# LR2051-901-input-panel.net
KiCad netlist of a schematic drawn in EAGLE
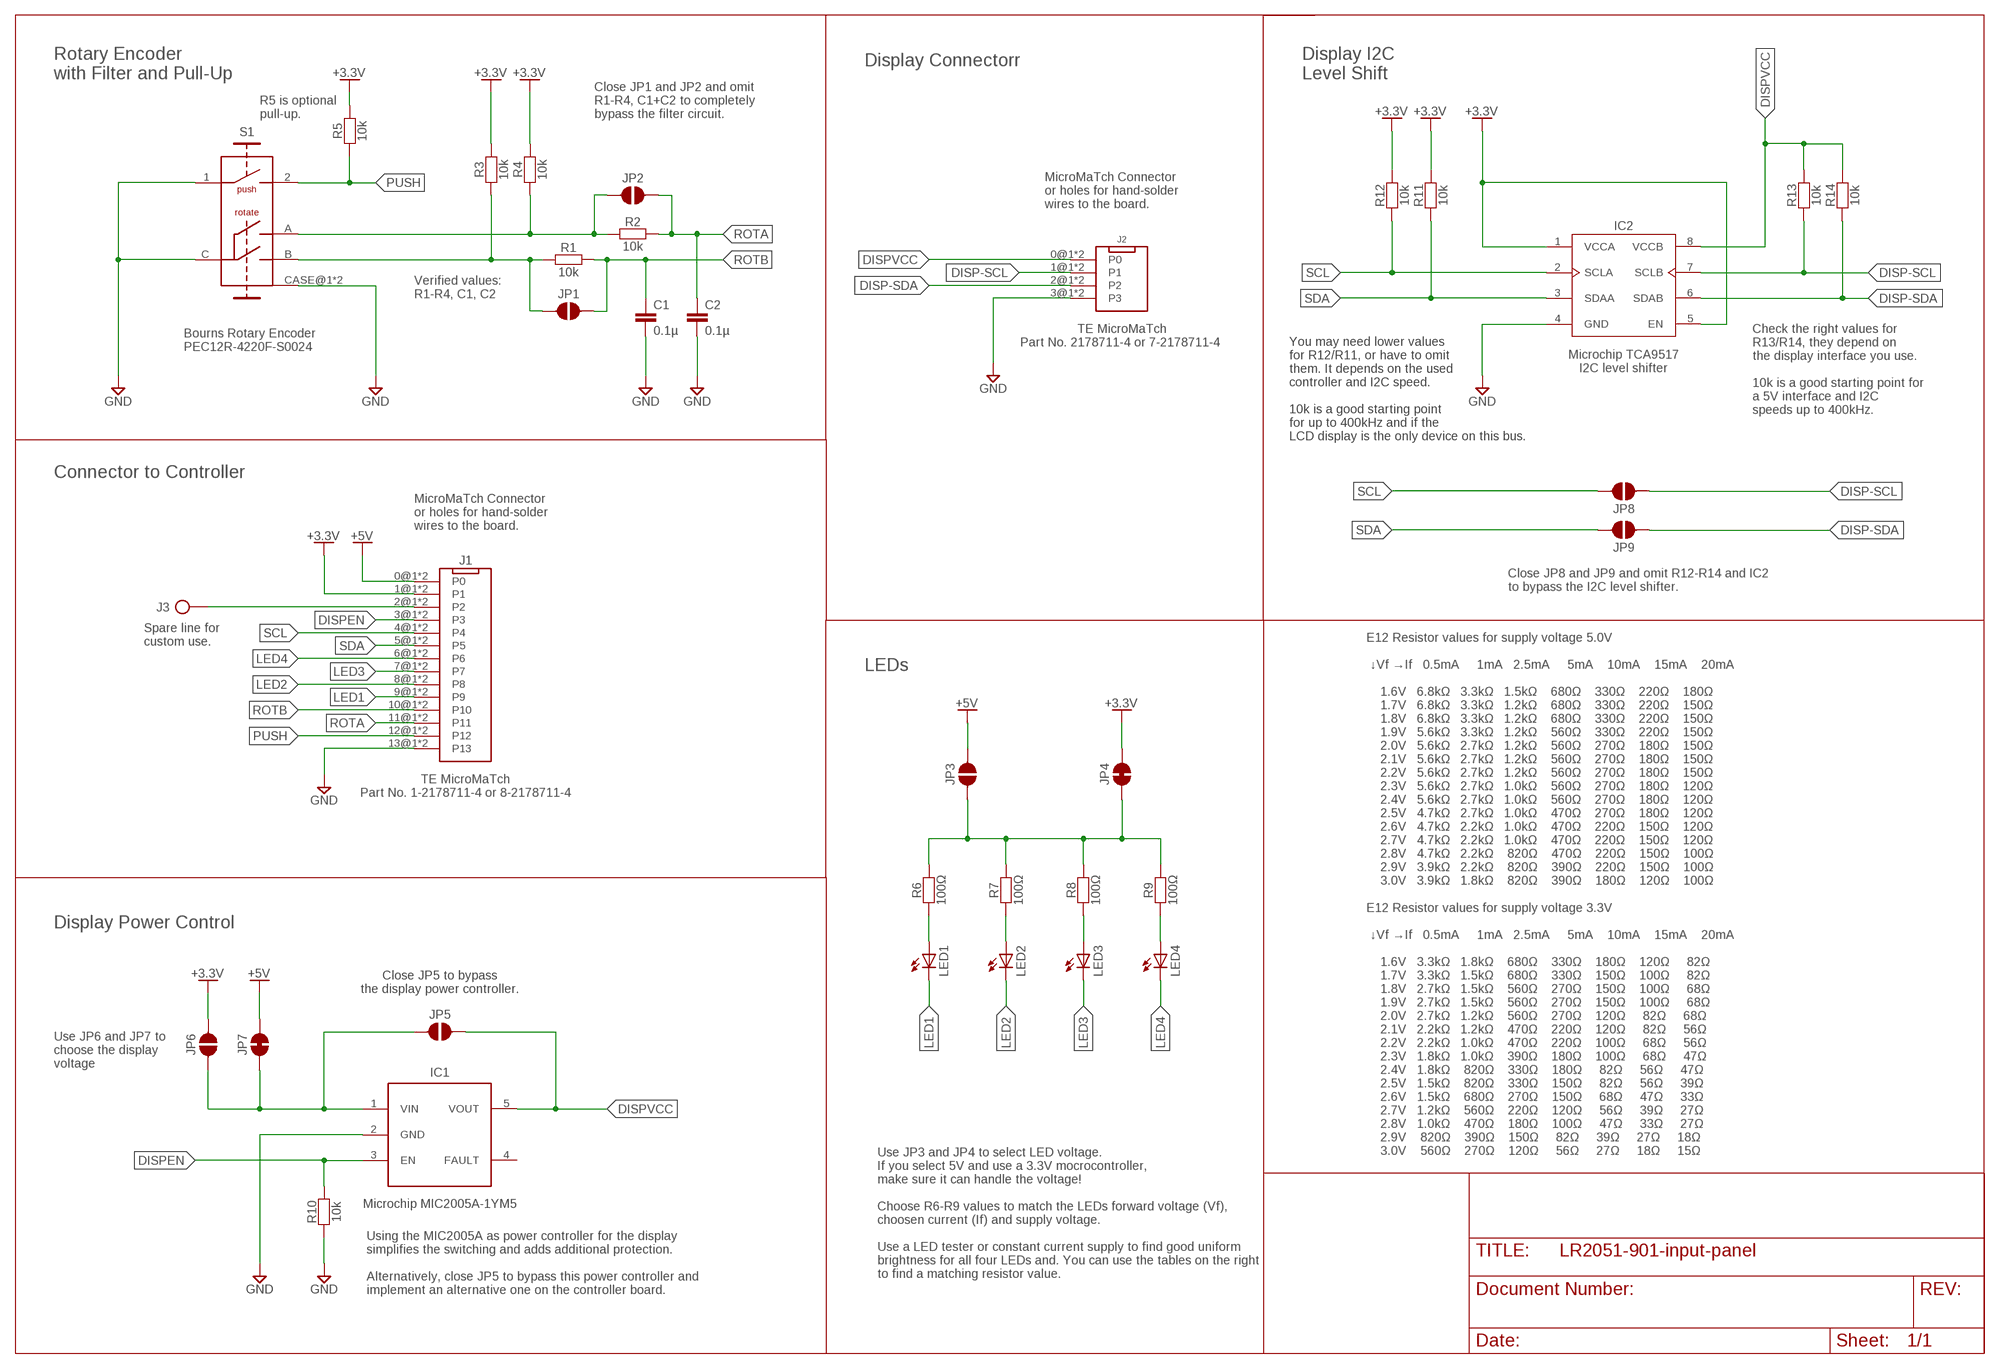
[diagram p0: schematic, sheet 1]

(export (version "E")
  (design (tool "Eeschema 10.0.6"))
  (components
    (comp (ref "C1")
      (value "0.1µ")
      (footprint "eagle-import:CAPACITOR-0805-VISHAY")
      (libsource (lib "eagle-import") (part "C0805-VISHAY"))
    )
    (comp (ref "C2")
      (value "0.1µ")
      (footprint "eagle-import:CAPACITOR-0805-VISHAY")
      (libsource (lib "eagle-import") (part "C0805-VISHAY"))
    )
    (comp (ref "IC1")
      (value "IC-MIC2005A-1YM5")
      (footprint "eagle-import:SOT23-5")
      (libsource (lib "eagle-import") (part "IC-MIC2005A-1YM5"))
    )
    (comp (ref "IC2")
      (value "IC-TCA9517")
      (footprint "eagle-import:SOIC127P599X175-8N")
      (libsource (lib "eagle-import") (part "IC-TCA9517"))
    )
    (comp (ref "J1")
      (value "CON-TE-MICROMATCH-14P-SMD+TH")
      (footprint "eagle-import:CON-TE-MICROMATCH-1-2178711-4+TH")
      (libsource (lib "eagle-import") (part "CON-TE-MICROMATCH-14P-SMD+TH"))
    )
    (comp (ref "J2")
      (value "CON-TE-MICROMATCH-4P-SMD+TH")
      (footprint "eagle-import:CON-TE-MICROMATCH-2178711-4+TH")
      (libsource (lib "eagle-import") (part "CON-TE-MICROMATCH-4P-SMD+TH"))
    )
    (comp (ref "J3")
      (value "CON-HOLE-D0.9")
      (footprint "eagle-import:CON-HOLE-D0.9")
      (libsource (lib "eagle-import") (part "CON-HOLE-D0.9"))
    )
    (comp (ref "JP1")
      (value "J-SMD-OFF")
      (footprint "eagle-import:J-SMD-OFF")
      (libsource (lib "eagle-import") (part "J-SMD-OFF"))
    )
    (comp (ref "JP2")
      (value "J-SMD-OFF")
      (footprint "eagle-import:J-SMD-OFF")
      (libsource (lib "eagle-import") (part "J-SMD-OFF"))
    )
    (comp (ref "JP3")
      (value "J-SMD-OFF")
      (footprint "eagle-import:J-SMD-OFF")
      (libsource (lib "eagle-import") (part "J-SMD-OFF"))
    )
    (comp (ref "JP4")
      (value "J-SMD-ON")
      (footprint "eagle-import:J-SMD-ON")
      (libsource (lib "eagle-import") (part "J-SMD-ON"))
    )
    (comp (ref "JP5")
      (value "J-SMD-OFF")
      (footprint "eagle-import:J-SMD-OFF")
      (libsource (lib "eagle-import") (part "J-SMD-OFF"))
    )
    (comp (ref "JP6")
      (value "J-SMD-OFF")
      (footprint "eagle-import:J-SMD-OFF")
      (libsource (lib "eagle-import") (part "J-SMD-OFF"))
    )
    (comp (ref "JP7")
      (value "J-SMD-ON")
      (footprint "eagle-import:J-SMD-ON")
      (libsource (lib "eagle-import") (part "J-SMD-ON"))
    )
    (comp (ref "JP8")
      (value "J-SMD-OFF")
      (footprint "eagle-import:J-SMD-OFF")
      (libsource (lib "eagle-import") (part "J-SMD-OFF"))
    )
    (comp (ref "JP9")
      (value "J-SMD-OFF")
      (footprint "eagle-import:J-SMD-OFF")
      (libsource (lib "eagle-import") (part "J-SMD-OFF"))
    )
    (comp (ref "LED1")
      (value "LED5MM")
      (footprint "eagle-import:LED5MM")
      (libsource (lib "eagle-import") (part "LED5MM"))
    )
    (comp (ref "LED2")
      (value "LED5MM")
      (footprint "eagle-import:LED5MM")
      (libsource (lib "eagle-import") (part "LED5MM"))
    )
    (comp (ref "LED3")
      (value "LED5MM")
      (footprint "eagle-import:LED5MM")
      (libsource (lib "eagle-import") (part "LED5MM"))
    )
    (comp (ref "LED4")
      (value "LED5MM")
      (footprint "eagle-import:LED5MM")
      (libsource (lib "eagle-import") (part "LED5MM"))
    )
    (comp (ref "R1")
      (value "10k")
      (footprint "eagle-import:R-0805-HANDSOLDER")
      (libsource (lib "eagle-import") (part "R-0805-HANDSOLDER"))
    )
    (comp (ref "R2")
      (value "10k")
      (footprint "eagle-import:R-0805-HANDSOLDER")
      (libsource (lib "eagle-import") (part "R-0805-HANDSOLDER"))
    )
    (comp (ref "R3")
      (value "10k")
      (footprint "eagle-import:R-0805-HANDSOLDER")
      (libsource (lib "eagle-import") (part "R-0805-HANDSOLDER"))
    )
    (comp (ref "R4")
      (value "10k")
      (footprint "eagle-import:R-0805-HANDSOLDER")
      (libsource (lib "eagle-import") (part "R-0805-HANDSOLDER"))
    )
    (comp (ref "R5")
      (value "10k")
      (footprint "eagle-import:R-0805-HANDSOLDER")
      (libsource (lib "eagle-import") (part "R-0805-HANDSOLDER"))
    )
    (comp (ref "R6")
      (value "100Ω")
      (footprint "eagle-import:R-0805-HANDSOLDER")
      (libsource (lib "eagle-import") (part "R-0805-HANDSOLDER"))
    )
    (comp (ref "R7")
      (value "100Ω")
      (footprint "eagle-import:R-0805-HANDSOLDER")
      (libsource (lib "eagle-import") (part "R-0805-HANDSOLDER"))
    )
    (comp (ref "R8")
      (value "100Ω")
      (footprint "eagle-import:R-0805-HANDSOLDER")
      (libsource (lib "eagle-import") (part "R-0805-HANDSOLDER"))
    )
    (comp (ref "R9")
      (value "100Ω")
      (footprint "eagle-import:R-0805-HANDSOLDER")
      (libsource (lib "eagle-import") (part "R-0805-HANDSOLDER"))
    )
    (comp (ref "R10")
      (value "10k")
      (footprint "eagle-import:R-0805-HANDSOLDER")
      (libsource (lib "eagle-import") (part "R-0805-HANDSOLDER"))
    )
    (comp (ref "R11")
      (value "10k")
      (footprint "eagle-import:R-0805-HANDSOLDER")
      (libsource (lib "eagle-import") (part "R-0805-HANDSOLDER"))
    )
    (comp (ref "R12")
      (value "10k")
      (footprint "eagle-import:R-0805-HANDSOLDER")
      (libsource (lib "eagle-import") (part "R-0805-HANDSOLDER"))
    )
    (comp (ref "R13")
      (value "10k")
      (footprint "eagle-import:R-0805-HANDSOLDER")
      (libsource (lib "eagle-import") (part "R-0805-HANDSOLDER"))
    )
    (comp (ref "R14")
      (value "10k")
      (footprint "eagle-import:R-0805-HANDSOLDER")
      (libsource (lib "eagle-import") (part "R-0805-HANDSOLDER"))
    )
    (comp (ref "S1")
      (value "ENC-BOURNS-PEC12R-4220F-S0024")
      (footprint "eagle-import:ENC-BOURNS-PEC12R-4220F-S0024")
      (libsource (lib "eagle-import") (part "ENC-BOURNS-PEC12R-4220F-S0024"))
    )
  )
  (nets
    (net (code "1") (name "+3.3V") (class "Default")
      (node (ref "IC2") (pin "1") (pinfunction "VCCA_1") (pintype "power_in"))
      (node (ref "IC2") (pin "5") (pinfunction "EN_5") (pintype "bidirectional"))
      (node (ref "J1") (pin "1@1") (pinfunction "P1_1@1") (pintype "bidirectional"))
      (node (ref "J1") (pin "1@2") (pinfunction "P1_1@2") (pintype "bidirectional"))
      (node (ref "JP4") (pin "2") (pinfunction "2_2") (pintype "passive"))
      (node (ref "JP6") (pin "2") (pinfunction "2_2") (pintype "passive"))
      (node (ref "R11") (pin "2") (pinfunction "P2_2") (pintype "passive"))
      (node (ref "R12") (pin "2") (pinfunction "P2_2") (pintype "passive"))
      (node (ref "R3") (pin "2") (pinfunction "P2_2") (pintype "passive"))
      (node (ref "R4") (pin "2") (pinfunction "P2_2") (pintype "passive"))
      (node (ref "R5") (pin "2") (pinfunction "P2_2") (pintype "passive"))
    )
    (net (code "2") (name "+5V") (class "Default")
      (node (ref "J1") (pin "0@1") (pinfunction "P0_0@1") (pintype "bidirectional"))
      (node (ref "J1") (pin "0@2") (pinfunction "P0_0@2") (pintype "bidirectional"))
      (node (ref "JP3") (pin "2") (pinfunction "2_2") (pintype "passive"))
      (node (ref "JP7") (pin "2") (pinfunction "2_2") (pintype "passive"))
    )
    (net (code "3") (name "DISP-SCL") (class "Default")
      (node (ref "IC2") (pin "7") (pinfunction "SCLB_7") (pintype "bidirectional"))
      (node (ref "J2") (pin "1@1") (pinfunction "P1_1@1") (pintype "bidirectional"))
      (node (ref "J2") (pin "1@2") (pinfunction "P1_1@2") (pintype "bidirectional"))
      (node (ref "JP8") (pin "1") (pinfunction "1_1") (pintype "passive"))
      (node (ref "R13") (pin "1") (pinfunction "P1_1") (pintype "passive"))
    )
    (net (code "4") (name "DISP-SDA") (class "Default")
      (node (ref "IC2") (pin "6") (pinfunction "SDAB_6") (pintype "bidirectional"))
      (node (ref "J2") (pin "2@1") (pinfunction "P2_2@1") (pintype "bidirectional"))
      (node (ref "J2") (pin "2@2") (pinfunction "P2_2@2") (pintype "bidirectional"))
      (node (ref "JP9") (pin "1") (pinfunction "1_1") (pintype "passive"))
      (node (ref "R14") (pin "1") (pinfunction "P1_1") (pintype "passive"))
    )
    (net (code "5") (name "DISPEN") (class "Default")
      (node (ref "IC1") (pin "3") (pinfunction "EN_3") (pintype "input"))
      (node (ref "J1") (pin "3@1") (pinfunction "P3_3@1") (pintype "bidirectional"))
      (node (ref "J1") (pin "3@2") (pinfunction "P3_3@2") (pintype "bidirectional"))
      (node (ref "R10") (pin "2") (pinfunction "P2_2") (pintype "passive"))
    )
    (net (code "6") (name "DISPVCC") (class "Default")
      (node (ref "IC1") (pin "5") (pinfunction "VOUT_5") (pintype "power_in"))
      (node (ref "IC2") (pin "8") (pinfunction "VCCB_8") (pintype "power_in"))
      (node (ref "J2") (pin "0@1") (pinfunction "P0_0@1") (pintype "bidirectional"))
      (node (ref "J2") (pin "0@2") (pinfunction "P0_0@2") (pintype "bidirectional"))
      (node (ref "JP5") (pin "2") (pinfunction "2_2") (pintype "passive"))
      (node (ref "R13") (pin "2") (pinfunction "P2_2") (pintype "passive"))
      (node (ref "R14") (pin "2") (pinfunction "P2_2") (pintype "passive"))
    )
    (net (code "7") (name "GND") (class "Default")
      (node (ref "C1") (pin "2") (pinfunction "2_2") (pintype "passive"))
      (node (ref "C2") (pin "2") (pinfunction "2_2") (pintype "passive"))
      (node (ref "IC1") (pin "2") (pinfunction "GND_2") (pintype "power_in"))
      (node (ref "IC2") (pin "4") (pinfunction "GND_4") (pintype "power_in"))
      (node (ref "J1") (pin "13@1") (pinfunction "P13_13@1") (pintype "bidirectional"))
      (node (ref "J1") (pin "13@2") (pinfunction "P13_13@2") (pintype "bidirectional"))
      (node (ref "J2") (pin "3@1") (pinfunction "P3_3@1") (pintype "bidirectional"))
      (node (ref "J2") (pin "3@2") (pinfunction "P3_3@2") (pintype "bidirectional"))
      (node (ref "R10") (pin "1") (pinfunction "P1_1") (pintype "passive"))
      (node (ref "S1") (pin "1") (pinfunction "S_1") (pintype "passive"))
      (node (ref "S1") (pin "C") (pinfunction "C_C") (pintype "passive"))
      (node (ref "S1") (pin "CASE@1") (pinfunction "GND_CASE@1") (pintype "power_in"))
      (node (ref "S1") (pin "CASE@2") (pinfunction "GND_CASE@2") (pintype "power_in"))
    )
    (net (code "8") (name "LED1") (class "Default")
      (node (ref "J1") (pin "9@1") (pinfunction "P9_9@1") (pintype "bidirectional"))
      (node (ref "J1") (pin "9@2") (pinfunction "P9_9@2") (pintype "bidirectional"))
      (node (ref "LED1") (pin "K") (pinfunction "C_K") (pintype "passive"))
    )
    (net (code "9") (name "LED2") (class "Default")
      (node (ref "J1") (pin "8@1") (pinfunction "P8_8@1") (pintype "bidirectional"))
      (node (ref "J1") (pin "8@2") (pinfunction "P8_8@2") (pintype "bidirectional"))
      (node (ref "LED2") (pin "K") (pinfunction "C_K") (pintype "passive"))
    )
    (net (code "10") (name "LED3") (class "Default")
      (node (ref "J1") (pin "7@1") (pinfunction "P7_7@1") (pintype "bidirectional"))
      (node (ref "J1") (pin "7@2") (pinfunction "P7_7@2") (pintype "bidirectional"))
      (node (ref "LED3") (pin "K") (pinfunction "C_K") (pintype "passive"))
    )
    (net (code "11") (name "LED4") (class "Default")
      (node (ref "J1") (pin "6@1") (pinfunction "P6_6@1") (pintype "bidirectional"))
      (node (ref "J1") (pin "6@2") (pinfunction "P6_6@2") (pintype "bidirectional"))
      (node (ref "LED4") (pin "K") (pinfunction "C_K") (pintype "passive"))
    )
    (net (code "12") (name "Net-(IC1-VIN)") (class "Default")
      (node (ref "IC1") (pin "1") (pinfunction "VIN_1") (pintype "power_in"))
      (node (ref "JP5") (pin "1") (pinfunction "1_1") (pintype "passive"))
      (node (ref "JP6") (pin "1") (pinfunction "1_1") (pintype "passive"))
      (node (ref "JP7") (pin "1") (pinfunction "1_1") (pintype "passive"))
    )
    (net (code "13") (name "Net-(J1-P2-Pad2@1)") (class "Default")
      (node (ref "J1") (pin "2@1") (pinfunction "P2_2@1") (pintype "bidirectional"))
      (node (ref "J1") (pin "2@2") (pinfunction "P2_2@2") (pintype "bidirectional"))
      (node (ref "J3") (pin "1") (pinfunction "1_1") (pintype "passive"))
    )
    (net (code "14") (name "Net-(R1-P1)") (class "Default")
      (node (ref "JP1") (pin "1") (pinfunction "1_1") (pintype "passive"))
      (node (ref "R1") (pin "1") (pinfunction "P1_1") (pintype "passive"))
      (node (ref "R3") (pin "1") (pinfunction "P1_1") (pintype "passive"))
      (node (ref "S1") (pin "B") (pinfunction "B_B") (pintype "passive"))
    )
    (net (code "15") (name "Net-(R2-P1)") (class "Default")
      (node (ref "JP2") (pin "1") (pinfunction "1_1") (pintype "passive"))
      (node (ref "R2") (pin "1") (pinfunction "P1_1") (pintype "passive"))
      (node (ref "R4") (pin "1") (pinfunction "P1_1") (pintype "passive"))
      (node (ref "S1") (pin "A") (pinfunction "A_A") (pintype "passive"))
    )
    (net (code "16") (name "Net-(R6-P1)") (class "Default")
      (node (ref "LED1") (pin "A") (pinfunction "A_A") (pintype "passive"))
      (node (ref "R6") (pin "1") (pinfunction "P1_1") (pintype "passive"))
    )
    (net (code "17") (name "Net-(R6-P2)") (class "Default")
      (node (ref "JP3") (pin "1") (pinfunction "1_1") (pintype "passive"))
      (node (ref "JP4") (pin "1") (pinfunction "1_1") (pintype "passive"))
      (node (ref "R6") (pin "2") (pinfunction "P2_2") (pintype "passive"))
      (node (ref "R7") (pin "2") (pinfunction "P2_2") (pintype "passive"))
      (node (ref "R8") (pin "2") (pinfunction "P2_2") (pintype "passive"))
      (node (ref "R9") (pin "2") (pinfunction "P2_2") (pintype "passive"))
    )
    (net (code "18") (name "Net-(R7-P1)") (class "Default")
      (node (ref "LED2") (pin "A") (pinfunction "A_A") (pintype "passive"))
      (node (ref "R7") (pin "1") (pinfunction "P1_1") (pintype "passive"))
    )
    (net (code "19") (name "Net-(R8-P1)") (class "Default")
      (node (ref "LED3") (pin "A") (pinfunction "A_A") (pintype "passive"))
      (node (ref "R8") (pin "1") (pinfunction "P1_1") (pintype "passive"))
    )
    (net (code "20") (name "Net-(R9-P1)") (class "Default")
      (node (ref "LED4") (pin "A") (pinfunction "A_A") (pintype "passive"))
      (node (ref "R9") (pin "1") (pinfunction "P1_1") (pintype "passive"))
    )
    (net (code "21") (name "PUSH") (class "Default")
      (node (ref "J1") (pin "12@1") (pinfunction "P12_12@1") (pintype "bidirectional"))
      (node (ref "J1") (pin "12@2") (pinfunction "P12_12@2") (pintype "bidirectional"))
      (node (ref "R5") (pin "1") (pinfunction "P1_1") (pintype "passive"))
      (node (ref "S1") (pin "2") (pinfunction "S_2") (pintype "passive"))
    )
    (net (code "22") (name "ROTA") (class "Default")
      (node (ref "C2") (pin "1") (pinfunction "1_1") (pintype "passive"))
      (node (ref "J1") (pin "11@1") (pinfunction "P11_11@1") (pintype "bidirectional"))
      (node (ref "J1") (pin "11@2") (pinfunction "P11_11@2") (pintype "bidirectional"))
      (node (ref "JP2") (pin "2") (pinfunction "2_2") (pintype "passive"))
      (node (ref "R2") (pin "2") (pinfunction "P2_2") (pintype "passive"))
    )
    (net (code "23") (name "ROTB") (class "Default")
      (node (ref "C1") (pin "1") (pinfunction "1_1") (pintype "passive"))
      (node (ref "J1") (pin "10@1") (pinfunction "P10_10@1") (pintype "bidirectional"))
      (node (ref "J1") (pin "10@2") (pinfunction "P10_10@2") (pintype "bidirectional"))
      (node (ref "JP1") (pin "2") (pinfunction "2_2") (pintype "passive"))
      (node (ref "R1") (pin "2") (pinfunction "P2_2") (pintype "passive"))
    )
    (net (code "24") (name "SCL") (class "Default")
      (node (ref "IC2") (pin "2") (pinfunction "SCLA_2") (pintype "bidirectional"))
      (node (ref "J1") (pin "4@1") (pinfunction "P4_4@1") (pintype "bidirectional"))
      (node (ref "J1") (pin "4@2") (pinfunction "P4_4@2") (pintype "bidirectional"))
      (node (ref "JP8") (pin "2") (pinfunction "2_2") (pintype "passive"))
      (node (ref "R12") (pin "1") (pinfunction "P1_1") (pintype "passive"))
    )
    (net (code "25") (name "SDA") (class "Default")
      (node (ref "IC2") (pin "3") (pinfunction "SDAA_3") (pintype "bidirectional"))
      (node (ref "J1") (pin "5@1") (pinfunction "P5_5@1") (pintype "bidirectional"))
      (node (ref "J1") (pin "5@2") (pinfunction "P5_5@2") (pintype "bidirectional"))
      (node (ref "JP9") (pin "2") (pinfunction "2_2") (pintype "passive"))
      (node (ref "R11") (pin "1") (pinfunction "P1_1") (pintype "passive"))
    )
    (net (code "26") (name "unconnected-(IC1-FAULT-Pad4)") (class "Default")
      (node (ref "IC1") (pin "4") (pinfunction "FAULT_4") (pintype "output"))
    )
  )
)
